# Motor_Control.net
KiCad netlist of a schematic drawn in Altium Designer
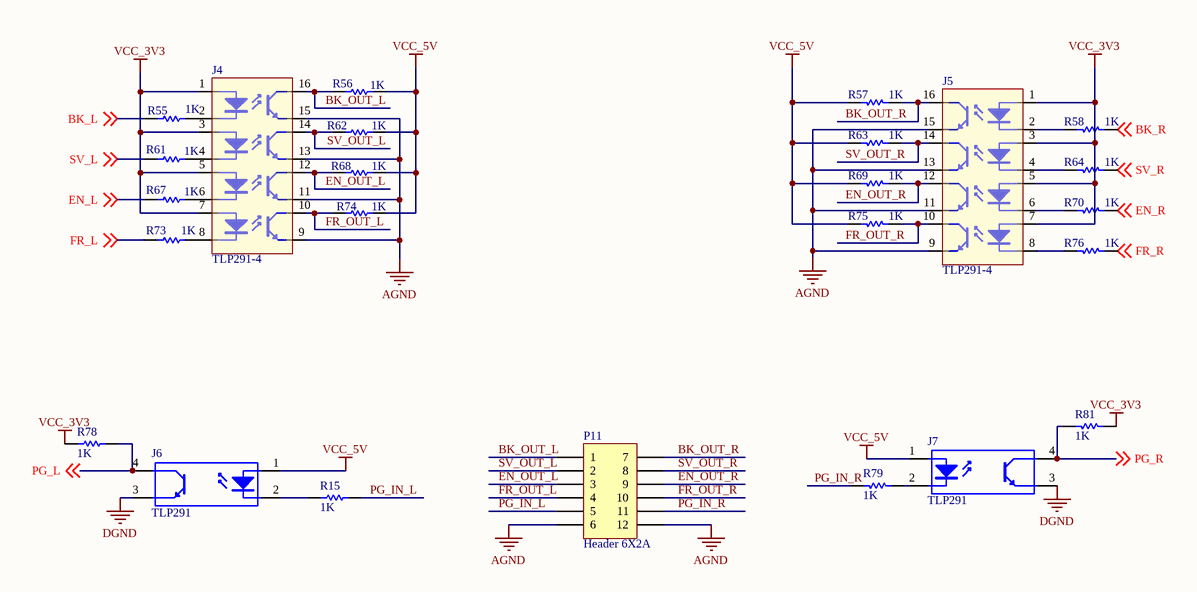
[diagram p0: Motor Control.SchDoc]

(export (version "E")
  (design (tool "Eeschema 10.0.6"))
  (components
    (comp (ref "J4")
      (value "TLP291-4")
      (description "光耦")
      (libsource (lib "Compiled_Libraries") (part "TLP291-4"))
    )
    (comp (ref "J5")
      (value "TLP291-4")
      (description "光耦")
      (libsource (lib "Compiled_Libraries") (part "TLP291-4"))
    )
    (comp (ref "J6")
      (value "TLP291")
      (footprint "SOP127P710X350-4N")
      (description "光耦")
      (fields (field (name "PUBLISHER") "Altium Limited"))
      (libsource (lib "Compiled_Libraries") (part "TLP291"))
    )
    (comp (ref "J7")
      (value "TLP291")
      (footprint "SOP127P710X350-4N")
      (description "光耦")
      (fields (field (name "PUBLISHER") "Altium Limited"))
      (libsource (lib "Compiled_Libraries") (part "TLP291"))
    )
    (comp (ref "P11")
      (value "Header 6X2A")
      (footprint "Molex-12P")
      (description "Header, 6-Pin, Dual row")
      (fields (field (name "PUBLISHER") "Altium Limited"))
      (libsource (lib "Miscellaneous Connectors") (part "Header 6X2A"))
    )
    (comp (ref "R15")
      (value "1K")
      (footprint "0805-1")
      (description "Resistor")
      (fields (field (name "Comment") "1K 5% 1/16W 0805") (field (name "PUBLISHER") "Altium Limited"))
      (libsource (lib "") (part "Res1_1"))
    )
    (comp (ref "R55")
      (value "1K")
      (footprint "0805-1")
      (description "Resistor")
      (fields (field (name "Comment") "1K 5% 1/16W 0805") (field (name "PUBLISHER") "Altium Limited"))
      (libsource (lib "boocax_schlib") (part "Res1"))
    )
    (comp (ref "R56")
      (value "1K")
      (footprint "0805-1")
      (description "Resistor")
      (fields (field (name "Comment") "1K 5% 1/16W 0805") (field (name "PUBLISHER") "Altium Limited"))
      (libsource (lib "boocax_schlib") (part "Res1"))
    )
    (comp (ref "R57")
      (value "1K")
      (footprint "0805-1")
      (description "Resistor")
      (fields (field (name "Comment") "1K 5% 1/16W 0805") (field (name "PUBLISHER") "Altium Limited"))
      (libsource (lib "boocax_schlib") (part "Res1"))
    )
    (comp (ref "R58")
      (value "1K")
      (footprint "0805-1")
      (description "Resistor")
      (fields (field (name "Comment") "1K 5% 1/16W 0805") (field (name "PUBLISHER") "Altium Limited"))
      (libsource (lib "boocax_schlib") (part "Res1"))
    )
    (comp (ref "R61")
      (value "1K")
      (footprint "0805-1")
      (description "Resistor")
      (fields (field (name "Comment") "1K 5% 1/16W 0805") (field (name "PUBLISHER") "Altium Limited"))
      (libsource (lib "boocax_schlib") (part "Res1"))
    )
    (comp (ref "R62")
      (value "1K")
      (footprint "0805-1")
      (description "Resistor")
      (fields (field (name "Comment") "1K 5% 1/16W 0805") (field (name "PUBLISHER") "Altium Limited"))
      (libsource (lib "boocax_schlib") (part "Res1"))
    )
    (comp (ref "R63")
      (value "1K")
      (footprint "0805-1")
      (description "Resistor")
      (fields (field (name "Comment") "1K 5% 1/16W 0805") (field (name "PUBLISHER") "Altium Limited"))
      (libsource (lib "boocax_schlib") (part "Res1"))
    )
    (comp (ref "R64")
      (value "1K")
      (footprint "0805-1")
      (description "Resistor")
      (fields (field (name "Comment") "1K 5% 1/16W 0805") (field (name "PUBLISHER") "Altium Limited"))
      (libsource (lib "boocax_schlib") (part "Res1"))
    )
    (comp (ref "R67")
      (value "1K")
      (footprint "0805-1")
      (description "Resistor")
      (fields (field (name "Comment") "1K 5% 1/16W 0805") (field (name "PUBLISHER") "Altium Limited"))
      (libsource (lib "boocax_schlib") (part "Res1"))
    )
    (comp (ref "R68")
      (value "1K")
      (footprint "0805-1")
      (description "Resistor")
      (fields (field (name "Comment") "1K 5% 1/16W 0805") (field (name "PUBLISHER") "Altium Limited"))
      (libsource (lib "boocax_schlib") (part "Res1"))
    )
    (comp (ref "R69")
      (value "1K")
      (footprint "0805-1")
      (description "Resistor")
      (fields (field (name "Comment") "1K 5% 1/16W 0805") (field (name "PUBLISHER") "Altium Limited"))
      (libsource (lib "boocax_schlib") (part "Res1"))
    )
    (comp (ref "R70")
      (value "1K")
      (footprint "0805-1")
      (description "Resistor")
      (fields (field (name "Comment") "1K 5% 1/16W 0805") (field (name "PUBLISHER") "Altium Limited"))
      (libsource (lib "boocax_schlib") (part "Res1"))
    )
    (comp (ref "R73")
      (value "1K")
      (footprint "0805-1")
      (description "Resistor")
      (fields (field (name "Comment") "1K 5% 1/16W 0805") (field (name "PUBLISHER") "Altium Limited"))
      (libsource (lib "boocax_schlib") (part "Res1"))
    )
    (comp (ref "R74")
      (value "1K")
      (footprint "0805-1")
      (description "Resistor")
      (fields (field (name "Comment") "1K 5% 1/16W 0805") (field (name "PUBLISHER") "Altium Limited"))
      (libsource (lib "boocax_schlib") (part "Res1"))
    )
    (comp (ref "R75")
      (value "1K")
      (footprint "0805-1")
      (description "Resistor")
      (fields (field (name "Comment") "1K 5% 1/16W 0805") (field (name "PUBLISHER") "Altium Limited"))
      (libsource (lib "boocax_schlib") (part "Res1"))
    )
    (comp (ref "R76")
      (value "1K")
      (footprint "0805-1")
      (description "Resistor")
      (fields (field (name "Comment") "1K 5% 1/16W 0805") (field (name "PUBLISHER") "Altium Limited"))
      (libsource (lib "boocax_schlib") (part "Res1"))
    )
    (comp (ref "R78")
      (value "1K")
      (footprint "0805-1")
      (description "Resistor")
      (fields (field (name "Comment") "1K 5% 1/16W 0805") (field (name "PUBLISHER") "Altium Limited"))
      (libsource (lib "") (part "Res1_1"))
    )
    (comp (ref "R79")
      (value "1K")
      (footprint "0805-1")
      (description "Resistor")
      (fields (field (name "Comment") "1K 5% 1/16W 0805") (field (name "PUBLISHER") "Altium Limited"))
      (libsource (lib "boocax_schlib") (part "Res1"))
    )
    (comp (ref "R81")
      (value "1K")
      (footprint "0805-1")
      (description "Resistor")
      (fields (field (name "Comment") "1K 5% 1/16W 0805") (field (name "PUBLISHER") "Altium Limited"))
      (libsource (lib "boocax_schlib") (part "Res1"))
    )
  )
  (nets
    (net (code "9") (name "/BK_OUT_L") (class "Default")
      (node (ref "J4") (pin "16") (pinfunction "C_16") (pintype "passive"))
      (node (ref "P11") (pin "1") (pinfunction "1_1") (pintype "passive"))
      (node (ref "R56") (pin "1") (pinfunction "1_1") (pintype "passive"))
    )
    (net (code "10") (name "/BK_OUT_R") (class "Default")
      (node (ref "J5") (pin "16") (pinfunction "C_16") (pintype "passive"))
      (node (ref "P11") (pin "7") (pinfunction "7_7") (pintype "passive"))
      (node (ref "R57") (pin "1") (pinfunction "1_1") (pintype "passive"))
    )
    (net (code "15") (name "/EN_OUT_L") (class "Default")
      (node (ref "J4") (pin "12") (pinfunction "C_12") (pintype "passive"))
      (node (ref "P11") (pin "3") (pinfunction "3_3") (pintype "passive"))
      (node (ref "R68") (pin "1") (pinfunction "1_1") (pintype "passive"))
    )
    (net (code "16") (name "/EN_OUT_R") (class "Default")
      (node (ref "J5") (pin "12") (pinfunction "C_12") (pintype "passive"))
      (node (ref "P11") (pin "9") (pinfunction "9_9") (pintype "passive"))
      (node (ref "R69") (pin "1") (pinfunction "1_1") (pintype "passive"))
    )
    (net (code "18") (name "/FR_OUT_L") (class "Default")
      (node (ref "J4") (pin "10") (pinfunction "C_10") (pintype "passive"))
      (node (ref "P11") (pin "4") (pinfunction "4_4") (pintype "passive"))
      (node (ref "R74") (pin "1") (pinfunction "1_1") (pintype "passive"))
    )
    (net (code "19") (name "/FR_OUT_R") (class "Default")
      (node (ref "J5") (pin "10") (pinfunction "C_10") (pintype "passive"))
      (node (ref "P11") (pin "10") (pinfunction "10_10") (pintype "passive"))
      (node (ref "R75") (pin "1") (pinfunction "1_1") (pintype "passive"))
    )
    (net (code "20") (name "/PG_IN_L") (class "Default")
      (node (ref "P11") (pin "5") (pinfunction "5_5") (pintype "passive"))
      (node (ref "R15") (pin "1") (pinfunction "1_1") (pintype "passive"))
    )
    (net (code "21") (name "/PG_IN_R") (class "Default")
      (node (ref "P11") (pin "11") (pinfunction "11_11") (pintype "passive"))
      (node (ref "R79") (pin "1") (pinfunction "1_1") (pintype "passive"))
    )
    (net (code "24") (name "/SV_OUT_L") (class "Default")
      (node (ref "J4") (pin "14") (pinfunction "C_14") (pintype "passive"))
      (node (ref "P11") (pin "2") (pinfunction "2_2") (pintype "passive"))
      (node (ref "R62") (pin "1") (pinfunction "1_1") (pintype "passive"))
    )
    (net (code "25") (name "/SV_OUT_R") (class "Default")
      (node (ref "J5") (pin "14") (pinfunction "C_14") (pintype "passive"))
      (node (ref "P11") (pin "8") (pinfunction "8_8") (pintype "passive"))
      (node (ref "R63") (pin "1") (pinfunction "1_1") (pintype "passive"))
    )
    (net (code "28") (name "AGND") (class "Default")
      (node (ref "J4") (pin "11") (pinfunction "E_11") (pintype "passive"))
      (node (ref "J4") (pin "13") (pinfunction "E_13") (pintype "passive"))
      (node (ref "J4") (pin "15") (pinfunction "E_15") (pintype "passive"))
      (node (ref "J4") (pin "9") (pinfunction "E_9") (pintype "passive"))
      (node (ref "J5") (pin "11") (pinfunction "E_11") (pintype "passive"))
      (node (ref "J5") (pin "13") (pinfunction "E_13") (pintype "passive"))
      (node (ref "J5") (pin "15") (pinfunction "E_15") (pintype "passive"))
      (node (ref "J5") (pin "9") (pinfunction "E_9") (pintype "passive"))
      (node (ref "P11") (pin "12") (pinfunction "12_12") (pintype "passive"))
      (node (ref "P11") (pin "6") (pinfunction "6_6") (pintype "passive"))
    )
    (net (code "29") (name "BK_L") (class "Default")
      (node (ref "R55") (pin "2") (pinfunction "2_2") (pintype "passive"))
    )
    (net (code "30") (name "BK_R") (class "Default")
      (node (ref "R58") (pin "2") (pinfunction "2_2") (pintype "passive"))
    )
    (net (code "31") (name "DGND") (class "Default")
      (node (ref "J6") (pin "3") (pinfunction "E_3") (pintype "passive"))
      (node (ref "J7") (pin "3") (pinfunction "E_3") (pintype "passive"))
    )
    (net (code "32") (name "EN_L") (class "Default")
      (node (ref "R67") (pin "2") (pinfunction "2_2") (pintype "passive"))
    )
    (net (code "33") (name "EN_R") (class "Default")
      (node (ref "R70") (pin "2") (pinfunction "2_2") (pintype "passive"))
    )
    (net (code "34") (name "FR_L") (class "Default")
      (node (ref "R73") (pin "2") (pinfunction "2_2") (pintype "passive"))
    )
    (net (code "35") (name "FR_R") (class "Default")
      (node (ref "R76") (pin "2") (pinfunction "2_2") (pintype "passive"))
    )
    (net (code "36") (name "Net-(J4-K-Pad2)") (class "Default")
      (node (ref "J4") (pin "2") (pinfunction "K_2") (pintype "passive"))
      (node (ref "R55") (pin "1") (pinfunction "1_1") (pintype "passive"))
    )
    (net (code "37") (name "Net-(J4-K-Pad4)") (class "Default")
      (node (ref "J4") (pin "4") (pinfunction "K_4") (pintype "passive"))
      (node (ref "R61") (pin "1") (pinfunction "1_1") (pintype "passive"))
    )
    (net (code "38") (name "Net-(J4-K-Pad6)") (class "Default")
      (node (ref "J4") (pin "6") (pinfunction "K_6") (pintype "passive"))
      (node (ref "R67") (pin "1") (pinfunction "1_1") (pintype "passive"))
    )
    (net (code "39") (name "Net-(J4-K-Pad8)") (class "Default")
      (node (ref "J4") (pin "8") (pinfunction "K_8") (pintype "passive"))
      (node (ref "R73") (pin "1") (pinfunction "1_1") (pintype "passive"))
    )
    (net (code "40") (name "Net-(J5-K-Pad2)") (class "Default")
      (node (ref "J5") (pin "2") (pinfunction "K_2") (pintype "passive"))
      (node (ref "R58") (pin "1") (pinfunction "1_1") (pintype "passive"))
    )
    (net (code "41") (name "Net-(J5-K-Pad4)") (class "Default")
      (node (ref "J5") (pin "4") (pinfunction "K_4") (pintype "passive"))
      (node (ref "R64") (pin "1") (pinfunction "1_1") (pintype "passive"))
    )
    (net (code "42") (name "Net-(J5-K-Pad6)") (class "Default")
      (node (ref "J5") (pin "6") (pinfunction "K_6") (pintype "passive"))
      (node (ref "R70") (pin "1") (pinfunction "1_1") (pintype "passive"))
    )
    (net (code "43") (name "Net-(J5-K-Pad8)") (class "Default")
      (node (ref "J5") (pin "8") (pinfunction "K_8") (pintype "passive"))
      (node (ref "R76") (pin "1") (pinfunction "1_1") (pintype "passive"))
    )
    (net (code "44") (name "Net-(J6-K)") (class "Default")
      (node (ref "J6") (pin "2") (pinfunction "K_2") (pintype "passive"))
      (node (ref "R15") (pin "2") (pinfunction "2_2") (pintype "passive"))
    )
    (net (code "45") (name "Net-(J7-K)") (class "Default")
      (node (ref "J7") (pin "2") (pinfunction "K_2") (pintype "passive"))
      (node (ref "R79") (pin "2") (pinfunction "2_2") (pintype "passive"))
    )
    (net (code "46") (name "PG_L") (class "Default")
      (node (ref "J6") (pin "4") (pinfunction "C_4") (pintype "passive"))
      (node (ref "R78") (pin "1") (pinfunction "1_1") (pintype "passive"))
    )
    (net (code "47") (name "PG_R") (class "Default")
      (node (ref "J7") (pin "4") (pinfunction "C_4") (pintype "passive"))
      (node (ref "R81") (pin "1") (pinfunction "1_1") (pintype "passive"))
    )
    (net (code "48") (name "SV_L") (class "Default")
      (node (ref "R61") (pin "2") (pinfunction "2_2") (pintype "passive"))
    )
    (net (code "49") (name "SV_R") (class "Default")
      (node (ref "R64") (pin "2") (pinfunction "2_2") (pintype "passive"))
    )
    (net (code "50") (name "VCC_3V3") (class "Default")
      (node (ref "J4") (pin "1") (pinfunction "A_1") (pintype "passive"))
      (node (ref "J4") (pin "3") (pinfunction "A_3") (pintype "passive"))
      (node (ref "J4") (pin "5") (pinfunction "A_5") (pintype "passive"))
      (node (ref "J4") (pin "7") (pinfunction "A_7") (pintype "passive"))
      (node (ref "J5") (pin "1") (pinfunction "A_1") (pintype "passive"))
      (node (ref "J5") (pin "3") (pinfunction "A_3") (pintype "passive"))
      (node (ref "J5") (pin "5") (pinfunction "A_5") (pintype "passive"))
      (node (ref "J5") (pin "7") (pinfunction "A_7") (pintype "passive"))
      (node (ref "R78") (pin "2") (pinfunction "2_2") (pintype "passive"))
      (node (ref "R81") (pin "2") (pinfunction "2_2") (pintype "passive"))
    )
    (net (code "51") (name "VCC_5V") (class "Default")
      (node (ref "J6") (pin "1") (pinfunction "A_1") (pintype "passive"))
      (node (ref "J7") (pin "1") (pinfunction "A_1") (pintype "passive"))
      (node (ref "R56") (pin "2") (pinfunction "2_2") (pintype "passive"))
      (node (ref "R57") (pin "2") (pinfunction "2_2") (pintype "passive"))
      (node (ref "R62") (pin "2") (pinfunction "2_2") (pintype "passive"))
      (node (ref "R63") (pin "2") (pinfunction "2_2") (pintype "passive"))
      (node (ref "R68") (pin "2") (pinfunction "2_2") (pintype "passive"))
      (node (ref "R69") (pin "2") (pinfunction "2_2") (pintype "passive"))
      (node (ref "R74") (pin "2") (pinfunction "2_2") (pintype "passive"))
      (node (ref "R75") (pin "2") (pinfunction "2_2") (pintype "passive"))
    )
  )
)
